# TPDH-Walrus.net
KiCad netlist of a schematic drawn in EAGLE
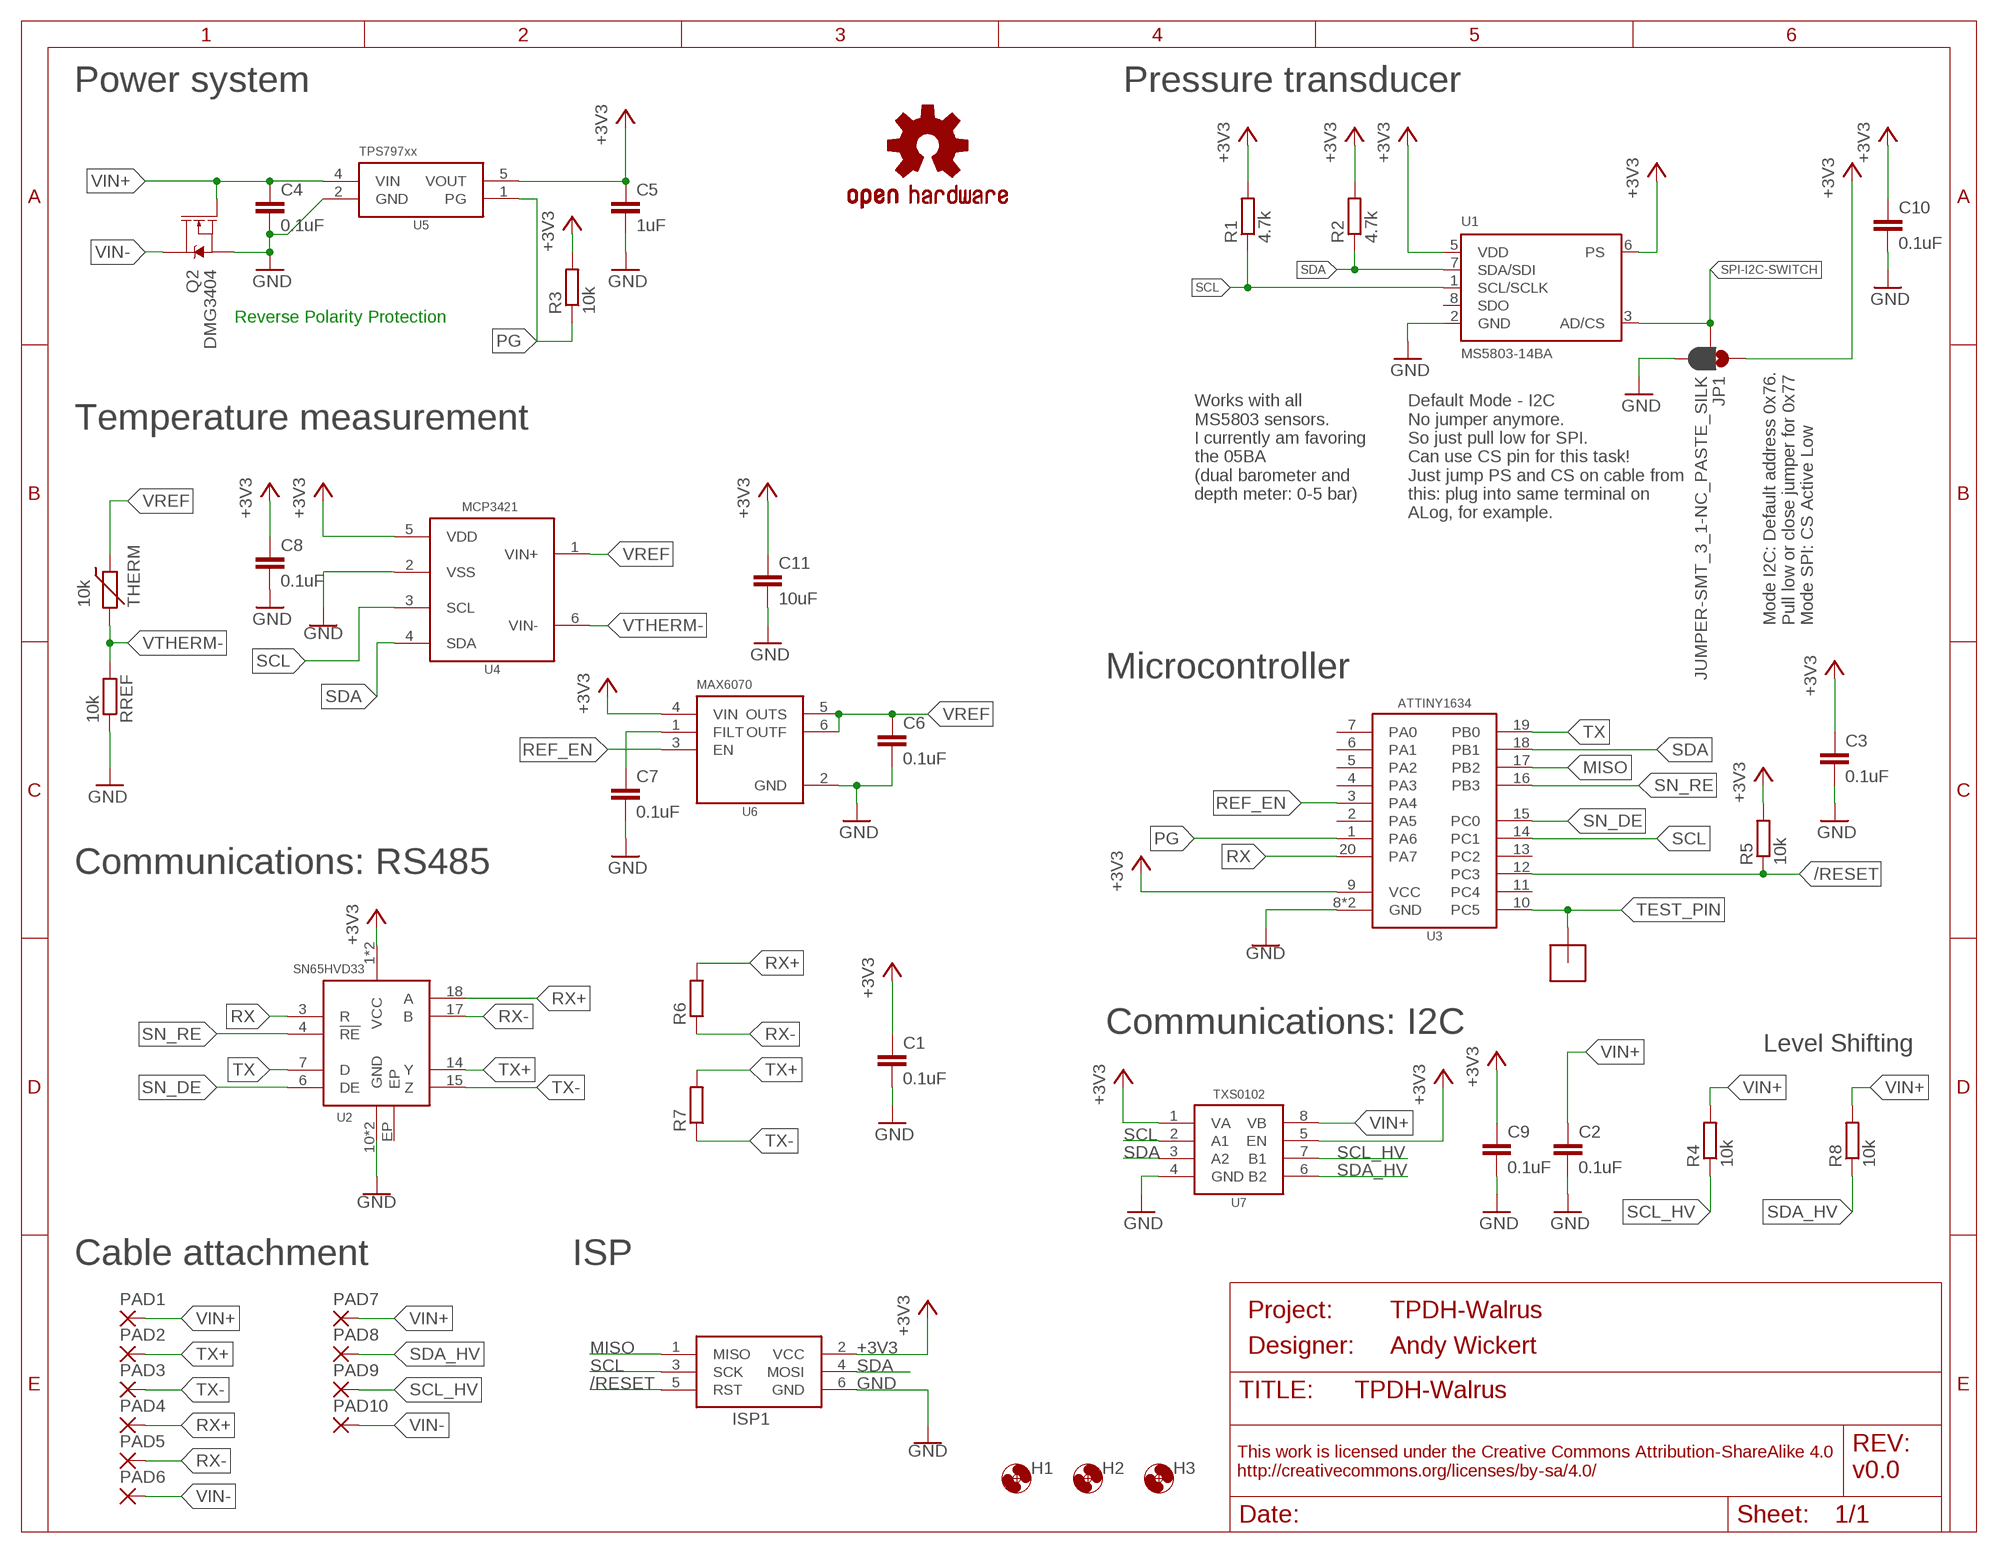
[diagram p0: schematic, sheet 1]

(export (version "E")
  (design (tool "Eeschema 10.0.6"))
  (components
    (comp (ref "C1")
      (value "0.1uF")
      (footprint "eagle-import:C0402")
      (fields (field (name "MF") "Murata") (field (name "MPN") "GCM155R71C104KA55D"))
      (libsource (lib "eagle-import") (part "C-EUC04020.1UF"))
    )
    (comp (ref "C2")
      (value "0.1uF")
      (footprint "eagle-import:C0402")
      (fields (field (name "MF") "Murata") (field (name "MPN") "GCM155R71C104KA55D"))
      (libsource (lib "eagle-import") (part "C-EUC04020.1UF"))
    )
    (comp (ref "C3")
      (value "0.1uF")
      (footprint "eagle-import:C0402")
      (fields (field (name "MF") "Murata") (field (name "MPN") "GCM155R71C104KA55D"))
      (libsource (lib "eagle-import") (part "C-EUC04020.1UF"))
    )
    (comp (ref "C4")
      (value "0.1uF")
      (footprint "eagle-import:C0402")
      (fields (field (name "MF") "Murata") (field (name "MPN") "GCM155R71C104KA55D"))
      (libsource (lib "eagle-import") (part "C-EUC04020.1UF"))
    )
    (comp (ref "C5")
      (value "1uF")
      (footprint "eagle-import:C0603")
      (fields (field (name "MF") "Murata") (field (name "MPN") "GRM188R61C105KA12D"))
      (libsource (lib "eagle-import") (part "bschulz_passives_C-EUC06031UF"))
    )
    (comp (ref "C6")
      (value "0.1uF")
      (footprint "eagle-import:C0402")
      (fields (field (name "MF") "Murata") (field (name "MPN") "GCM155R71C104KA55D"))
      (libsource (lib "eagle-import") (part "C-EUC04020.1UF"))
    )
    (comp (ref "C7")
      (value "0.1uF")
      (footprint "eagle-import:C0402")
      (fields (field (name "MF") "Murata") (field (name "MPN") "GCM155R71C104KA55D"))
      (libsource (lib "eagle-import") (part "C-EUC04020.1UF"))
    )
    (comp (ref "C8")
      (value "0.1uF")
      (footprint "eagle-import:C0402")
      (fields (field (name "MF") "Murata") (field (name "MPN") "GCM155R71C104KA55D"))
      (libsource (lib "eagle-import") (part "C-EUC04020.1UF"))
    )
    (comp (ref "C9")
      (value "0.1uF")
      (footprint "eagle-import:C0402")
      (fields (field (name "MF") "Murata") (field (name "MPN") "GCM155R71C104KA55D"))
      (libsource (lib "eagle-import") (part "C-EUC04020.1UF"))
    )
    (comp (ref "C10")
      (value "0.1uF")
      (footprint "eagle-import:C0402")
      (fields (field (name "MF") "Murata") (field (name "MPN") "GCM155R71C104KA55D"))
      (libsource (lib "eagle-import") (part "C-EUC04020.1UF"))
    )
    (comp (ref "C11")
      (value "10uF")
      (footprint "eagle-import:C0805")
      (fields (field (name "MF") "Samsung") (field (name "MPN") "CL21A106KQCLRNC"))
      (libsource (lib "eagle-import") (part "C-EUC080510UF"))
    )
    (comp (ref "H1")
      (value "MOUNTING_HOLE2_NP")
      (footprint "eagle-import:2_56")
      (libsource (lib "eagle-import") (part "MOUNTING_HOLE2_NP"))
    )
    (comp (ref "H2")
      (value "MOUNTING_HOLE2_NP")
      (footprint "eagle-import:2_56")
      (libsource (lib "eagle-import") (part "MOUNTING_HOLE2_NP"))
    )
    (comp (ref "H3")
      (value "MOUNTING_HOLE2_NP")
      (footprint "eagle-import:2_56")
      (libsource (lib "eagle-import") (part "MOUNTING_HOLE2_NP"))
    )
    (comp (ref "ISP1")
      (value "AVRISP-6")
      (footprint "eagle-import:AVRISP")
      (libsource (lib "eagle-import") (part "AVRISP-6"))
    )
    (comp (ref "JP1")
      (value "JUMPER-SMT_3_1-NC_PASTE_SILK")
      (footprint "eagle-import:SMT-JUMPER_3_1-NC_PASTE_SILK")
      (libsource (lib "eagle-import") (part "JUMPER-SMT_3_1-NC_PASTE_SILK"))
    )
    (comp (ref "LOGO1")
      (value "OSHW-LOGOM")
      (footprint "eagle-import:OSHW-LOGO-M")
      (libsource (lib "eagle-import") (part "OSHW-LOGOM"))
    )
    (comp (ref "PAD1")
      (value "2,15/1,0")
      (footprint "eagle-import:2,15_1,0")
      (libsource (lib "eagle-import") (part "2,15/1,0"))
    )
    (comp (ref "PAD2")
      (value "2,15/1,0")
      (footprint "eagle-import:2,15_1,0")
      (libsource (lib "eagle-import") (part "2,15/1,0"))
    )
    (comp (ref "PAD3")
      (value "2,15/1,0")
      (footprint "eagle-import:2,15_1,0")
      (libsource (lib "eagle-import") (part "2,15/1,0"))
    )
    (comp (ref "PAD4")
      (value "2,15/1,0")
      (footprint "eagle-import:2,15_1,0")
      (libsource (lib "eagle-import") (part "2,15/1,0"))
    )
    (comp (ref "PAD5")
      (value "2,15/1,0")
      (footprint "eagle-import:2,15_1,0")
      (libsource (lib "eagle-import") (part "2,15/1,0"))
    )
    (comp (ref "PAD6")
      (value "2,15/1,0")
      (footprint "eagle-import:2,15_1,0")
      (libsource (lib "eagle-import") (part "2,15/1,0"))
    )
    (comp (ref "PAD7")
      (value "2,15/1,0")
      (footprint "eagle-import:2,15_1,0")
      (libsource (lib "eagle-import") (part "2,15/1,0"))
    )
    (comp (ref "PAD8")
      (value "2,15/1,0")
      (footprint "eagle-import:2,15_1,0")
      (libsource (lib "eagle-import") (part "2,15/1,0"))
    )
    (comp (ref "PAD9")
      (value "2,15/1,0")
      (footprint "eagle-import:2,15_1,0")
      (libsource (lib "eagle-import") (part "2,15/1,0"))
    )
    (comp (ref "PAD10")
      (value "2,15/1,0")
      (footprint "eagle-import:2,15_1,0")
      (libsource (lib "eagle-import") (part "2,15/1,0"))
    )
    (comp (ref "Q2")
      (value "DMG3404")
      (footprint "eagle-import:SOT23-3")
      (fields (field (name "MF") "Diodes Incorporated") (field (name "MPN") "DMG3404L-7"))
      (libsource (lib "eagle-import") (part "MOSFET-NCH-DMG3404L"))
    )
    (comp (ref "R1")
      (value "4.7k")
      (footprint "eagle-import:R0402")
      (fields (field (name "MF") "Yageo") (field (name "MPN") "RC0402JR-074K7L"))
      (libsource (lib "eagle-import") (part "R-EU_R04024.7K"))
    )
    (comp (ref "R2")
      (value "4.7k")
      (footprint "eagle-import:R0402")
      (fields (field (name "MF") "Yageo") (field (name "MPN") "RC0402JR-074K7L"))
      (libsource (lib "eagle-import") (part "R-EU_R04024.7K"))
    )
    (comp (ref "R3")
      (value "10k")
      (footprint "eagle-import:R0402")
      (fields (field (name "MF") "Yageo") (field (name "MPN") "RC0402JR-0710KL"))
      (libsource (lib "eagle-import") (part "R-EU_R040210K"))
    )
    (comp (ref "R4")
      (value "10k")
      (footprint "eagle-import:R0402")
      (fields (field (name "MF") "Yageo") (field (name "MPN") "RC0402JR-0710KL"))
      (libsource (lib "eagle-import") (part "R-EU_R040210K"))
    )
    (comp (ref "R5")
      (value "10k")
      (footprint "eagle-import:R0402")
      (fields (field (name "MF") "Yageo") (field (name "MPN") "RC0402JR-0710KL"))
      (libsource (lib "eagle-import") (part "R-EU_R040210K"))
    )
    (comp (ref "R6")
      (value "R-EU_100R0402")
      (footprint "eagle-import:R0402")
      (fields
        (field (name "MF") "Yageo")
        (field (name "MPN") "RC0402FR-07100RL")
        (field (name "VALUE_PART") "100")
      )
      (libsource (lib "eagle-import") (part "R-EU_R0402100"))
    )
    (comp (ref "R7")
      (value "R-EU_100R0402")
      (footprint "eagle-import:R0402")
      (fields
        (field (name "MF") "Yageo")
        (field (name "MPN") "RC0402FR-07100RL")
        (field (name "VALUE_PART") "100")
      )
      (libsource (lib "eagle-import") (part "R-EU_R0402100"))
    )
    (comp (ref "R8")
      (value "10k")
      (footprint "eagle-import:R0402")
      (fields (field (name "MF") "Yageo") (field (name "MPN") "RC0402JR-0710KL"))
      (libsource (lib "eagle-import") (part "R-EU_R040210K"))
    )
    (comp (ref "RREF")
      (value "10k")
      (footprint "eagle-import:R0603")
      (fields
        (field (name "MF") "Panasonic")
        (field (name "MPN") "ERA-3AEB103V")
        (field (name "DIGIKEY") "P10KDBCT-ND")
        (field (name "MF_1") "Panasonic")
        (field (name "MPN_1") "ERA-3AEB103V")
      )
      (libsource (lib "eagle-import") (part "R-EU_R0603P10K"))
    )
    (comp (ref "THERM")
      (value "10k")
      (footprint "eagle-import:R0603")
      (fields
        (field (name "MF") "Murata")
        (field (name "MPN") "NCU18XH103F60RB")
        (field (name "MF_1") "Murata")
      )
      (libsource (lib "eagle-import") (part "THERMISTOR10K"))
    )
    (comp (ref "U$12")
      (value "POGO_PAD")
      (footprint "eagle-import:POGO_PAD")
      (libsource (lib "eagle-import") (part "POGO_PAD"))
    )
    (comp (ref "U1")
      (value "MS5803-14BA")
      (footprint "eagle-import:MS5803")
      (fields (field (name "MF") "TE") (field (name "MPN") "MS580305BA01-00"))
      (libsource (lib "eagle-import") (part "MS5803-14BA"))
    )
    (comp (ref "U2")
      (value "SN65HVD33RHL")
      (footprint "eagle-import:VQFN-20_POWER")
      (fields (field (name "MF") "TI") (field (name "MPN") "SN65HVD33RHLR"))
      (libsource (lib "eagle-import") (part "SN65HVD33RHL"))
    )
    (comp (ref "U3")
      (value "ATTINY1634QFN")
      (footprint "eagle-import:QFN20")
      (fields (field (name "MF") "Atmel") (field (name "MPN") "ATTINY1634-MUR"))
      (libsource (lib "eagle-import") (part "ATTINY1634QFN"))
    )
    (comp (ref "U4")
      (value "MCP3421A3")
      (footprint "eagle-import:SOT23-6L")
      (fields
        (field (name "DISP") "MCP3421")
        (field (name "MF") "Microchip")
        (field (name "MPN") "MCP3421A3T-E/CH")
      )
      (libsource (lib "eagle-import") (part "MCP3421A3"))
    )
    (comp (ref "U5")
      (value "TPS79733")
      (footprint "eagle-import:DCK_R-PDSO-G5")
      (fields (field (name "MF") "TI") (field (name "MPN") "TPS79733DCKR"))
      (libsource (lib "eagle-import") (part "TPS79733"))
    )
    (comp (ref "U6")
      (value "MAX6070AAUT18")
      (footprint "eagle-import:SOT23-6L")
      (fields (field (name "MF") "Maxim") (field (name "MPN") "MAX6070BAUT18+T"))
      (libsource (lib "eagle-import") (part "MAX6070AAUT18"))
    )
    (comp (ref "U7")
      (value "TXS0102DQM")
      (footprint "eagle-import:DQM_R-PX2SON-N8")
      (fields (field (name "MF") "TI") (field (name "MPN") "TXS0102DQMR"))
      (libsource (lib "eagle-import") (part "TXS0102DQM"))
    )
  )
  (nets
    (net (code "1") (name "+3V3") (class "Default")
      (node (ref "C1") (pin "1") (pinfunction "1_1") (pintype "passive"))
      (node (ref "C10") (pin "1") (pinfunction "1_1") (pintype "passive"))
      (node (ref "C11") (pin "1") (pinfunction "1_1") (pintype "passive"))
      (node (ref "C3") (pin "1") (pinfunction "1_1") (pintype "passive"))
      (node (ref "C5") (pin "1") (pinfunction "1_1") (pintype "passive"))
      (node (ref "C8") (pin "1") (pinfunction "1_1") (pintype "passive"))
      (node (ref "C9") (pin "1") (pinfunction "1_1") (pintype "passive"))
      (node (ref "ISP1") (pin "2") (pinfunction "VCC_2") (pintype "power_in"))
      (node (ref "JP1") (pin "1") (pinfunction "1_1") (pintype "passive"))
      (node (ref "R1") (pin "2") (pinfunction "2_2") (pintype "passive"))
      (node (ref "R2") (pin "2") (pinfunction "2_2") (pintype "passive"))
      (node (ref "R3") (pin "2") (pinfunction "2_2") (pintype "passive"))
      (node (ref "R5") (pin "2") (pinfunction "2_2") (pintype "passive"))
      (node (ref "U1") (pin "5") (pinfunction "VDD_5") (pintype "bidirectional"))
      (node (ref "U1") (pin "6") (pinfunction "PS_6") (pintype "bidirectional"))
      (node (ref "U2") (pin "1") (pinfunction "VCC_1") (pintype "power_in"))
      (node (ref "U2") (pin "20") (pinfunction "VCC_20") (pintype "power_in"))
      (node (ref "U3") (pin "9") (pinfunction "VCC_9") (pintype "power_in"))
      (node (ref "U4") (pin "5") (pinfunction "VDD_5") (pintype "passive"))
      (node (ref "U5") (pin "5") (pinfunction "VOUT_5") (pintype "bidirectional"))
      (node (ref "U6") (pin "4") (pinfunction "VIN_4") (pintype "bidirectional"))
      (node (ref "U7") (pin "1") (pinfunction "VA_1") (pintype "power_in"))
      (node (ref "U7") (pin "5") (pinfunction "EN_5") (pintype "input"))
    )
    (net (code "2") (name "GND") (class "Default")
      (node (ref "C1") (pin "2") (pinfunction "2_2") (pintype "passive"))
      (node (ref "C10") (pin "2") (pinfunction "2_2") (pintype "passive"))
      (node (ref "C11") (pin "2") (pinfunction "2_2") (pintype "passive"))
      (node (ref "C2") (pin "2") (pinfunction "2_2") (pintype "passive"))
      (node (ref "C3") (pin "2") (pinfunction "2_2") (pintype "passive"))
      (node (ref "C4") (pin "2") (pinfunction "2_2") (pintype "passive"))
      (node (ref "C5") (pin "2") (pinfunction "2_2") (pintype "passive"))
      (node (ref "C6") (pin "2") (pinfunction "2_2") (pintype "passive"))
      (node (ref "C7") (pin "2") (pinfunction "2_2") (pintype "passive"))
      (node (ref "C8") (pin "2") (pinfunction "2_2") (pintype "passive"))
      (node (ref "C9") (pin "2") (pinfunction "2_2") (pintype "passive"))
      (node (ref "ISP1") (pin "6") (pinfunction "GND_6") (pintype "power_in"))
      (node (ref "JP1") (pin "3") (pinfunction "3_3") (pintype "passive"))
      (node (ref "Q2") (pin "2") (pinfunction "S_2") (pintype "bidirectional"))
      (node (ref "RREF") (pin "1") (pinfunction "1_1") (pintype "passive"))
      (node (ref "U1") (pin "2") (pinfunction "GND_2") (pintype "bidirectional"))
      (node (ref "U2") (pin "10") (pinfunction "GND_10") (pintype "power_in"))
      (node (ref "U2") (pin "11") (pinfunction "GND_11") (pintype "power_in"))
      (node (ref "U3") (pin "8") (pinfunction "GND_8") (pintype "power_in"))
      (node (ref "U3") (pin "EP") (pinfunction "GND_EP") (pintype "power_in"))
      (node (ref "U4") (pin "2") (pinfunction "VSS_2") (pintype "passive"))
      (node (ref "U5") (pin "2") (pinfunction "GND_2") (pintype "bidirectional"))
      (node (ref "U6") (pin "2") (pinfunction "GND_2") (pintype "bidirectional"))
      (node (ref "U7") (pin "4") (pinfunction "GND_4") (pintype "power_in"))
    )
    (net (code "3") (name "MISO") (class "Default")
      (node (ref "ISP1") (pin "1") (pinfunction "MISO_1") (pintype "input"))
      (node (ref "U3") (pin "17") (pinfunction "PB2_17") (pintype "bidirectional"))
    )
    (net (code "4") (name "Net-(U6-FILT)") (class "Default")
      (node (ref "C7") (pin "1") (pinfunction "1_1") (pintype "passive"))
      (node (ref "U6") (pin "1") (pinfunction "FILT_1") (pintype "bidirectional"))
    )
    (net (code "5") (name "PG") (class "Default")
      (node (ref "R3") (pin "1") (pinfunction "1_1") (pintype "passive"))
      (node (ref "U3") (pin "1") (pinfunction "PA6_1") (pintype "bidirectional"))
      (node (ref "U5") (pin "1") (pinfunction "PG_1") (pintype "bidirectional"))
    )
    (net (code "6") (name "REF_EN") (class "Default")
      (node (ref "U3") (pin "3") (pinfunction "PA4_3") (pintype "bidirectional"))
      (node (ref "U6") (pin "3") (pinfunction "EN_3") (pintype "bidirectional"))
    )
    (net (code "7") (name "RX") (class "Default")
      (node (ref "U2") (pin "3") (pinfunction "R_3") (pintype "output"))
      (node (ref "U3") (pin "20") (pinfunction "PA7_20") (pintype "bidirectional"))
    )
    (net (code "8") (name "RX+") (class "Default")
      (node (ref "PAD4") (pin "1") (pinfunction "P_1") (pintype "passive"))
      (node (ref "R6") (pin "2") (pinfunction "2_2") (pintype "passive"))
      (node (ref "U2") (pin "18") (pinfunction "A_18") (pintype "bidirectional"))
    )
    (net (code "9") (name "RX-") (class "Default")
      (node (ref "PAD5") (pin "1") (pinfunction "P_1") (pintype "passive"))
      (node (ref "R6") (pin "1") (pinfunction "1_1") (pintype "passive"))
      (node (ref "U2") (pin "17") (pinfunction "B_17") (pintype "bidirectional"))
    )
    (net (code "10") (name "SCL") (class "Default")
      (node (ref "ISP1") (pin "3") (pinfunction "SCK_3") (pintype "output"))
      (node (ref "R1") (pin "1") (pinfunction "1_1") (pintype "passive"))
      (node (ref "U1") (pin "1") (pinfunction "SCL/SCLK_1") (pintype "bidirectional"))
      (node (ref "U3") (pin "14") (pinfunction "PC1_14") (pintype "bidirectional"))
      (node (ref "U4") (pin "3") (pinfunction "SCL_3") (pintype "bidirectional"))
      (node (ref "U7") (pin "2") (pinfunction "A1_2") (pintype "bidirectional"))
    )
    (net (code "11") (name "SCL_HV") (class "Default")
      (node (ref "PAD9") (pin "1") (pinfunction "P_1") (pintype "passive"))
      (node (ref "R4") (pin "1") (pinfunction "1_1") (pintype "passive"))
      (node (ref "U7") (pin "7") (pinfunction "B1_7") (pintype "bidirectional"))
    )
    (net (code "12") (name "SDA") (class "Default")
      (node (ref "ISP1") (pin "4") (pinfunction "MOSI_4") (pintype "output"))
      (node (ref "R2") (pin "1") (pinfunction "1_1") (pintype "passive"))
      (node (ref "U1") (pin "7") (pinfunction "SDA/SDI_7") (pintype "bidirectional"))
      (node (ref "U3") (pin "18") (pinfunction "PB1_18") (pintype "bidirectional"))
      (node (ref "U4") (pin "4") (pinfunction "SDA_4") (pintype "bidirectional"))
      (node (ref "U7") (pin "3") (pinfunction "A2_3") (pintype "bidirectional"))
    )
    (net (code "13") (name "SDA_HV") (class "Default")
      (node (ref "PAD8") (pin "1") (pinfunction "P_1") (pintype "passive"))
      (node (ref "R8") (pin "1") (pinfunction "1_1") (pintype "passive"))
      (node (ref "U7") (pin "6") (pinfunction "B2_6") (pintype "bidirectional"))
    )
    (net (code "14") (name "SN_DE") (class "Default")
      (node (ref "U2") (pin "6") (pinfunction "DE_6") (pintype "input"))
      (node (ref "U3") (pin "15") (pinfunction "PC0_15") (pintype "bidirectional"))
    )
    (net (code "15") (name "SN_RE") (class "Default")
      (node (ref "U2") (pin "4") (pinfunction "~{RE}_4") (pintype "input"))
      (node (ref "U3") (pin "16") (pinfunction "PB3_16") (pintype "bidirectional"))
    )
    (net (code "16") (name "SPI-I2C-SWITCH") (class "Default")
      (node (ref "JP1") (pin "2") (pinfunction "2_2") (pintype "passive"))
      (node (ref "U1") (pin "3") (pinfunction "AD/CS_3") (pintype "bidirectional"))
    )
    (net (code "17") (name "TEST_PIN") (class "Default")
      (node (ref "U$12") (pin "P$1") (pinfunction "P$1_P$1") (pintype "bidirectional"))
      (node (ref "U3") (pin "10") (pinfunction "PC5_10") (pintype "bidirectional"))
    )
    (net (code "18") (name "TX") (class "Default")
      (node (ref "U2") (pin "7") (pinfunction "D_7") (pintype "input"))
      (node (ref "U3") (pin "19") (pinfunction "PB0_19") (pintype "bidirectional"))
    )
    (net (code "19") (name "TX+") (class "Default")
      (node (ref "PAD2") (pin "1") (pinfunction "P_1") (pintype "passive"))
      (node (ref "R7") (pin "2") (pinfunction "2_2") (pintype "passive"))
      (node (ref "U2") (pin "14") (pinfunction "Y_14") (pintype "bidirectional"))
    )
    (net (code "20") (name "TX-") (class "Default")
      (node (ref "PAD3") (pin "1") (pinfunction "P_1") (pintype "passive"))
      (node (ref "R7") (pin "1") (pinfunction "1_1") (pintype "passive"))
      (node (ref "U2") (pin "15") (pinfunction "Z_15") (pintype "bidirectional"))
    )
    (net (code "21") (name "VIN+") (class "Default")
      (node (ref "C2") (pin "1") (pinfunction "1_1") (pintype "passive"))
      (node (ref "C4") (pin "1") (pinfunction "1_1") (pintype "passive"))
      (node (ref "PAD1") (pin "1") (pinfunction "P_1") (pintype "passive"))
      (node (ref "PAD7") (pin "1") (pinfunction "P_1") (pintype "passive"))
      (node (ref "Q2") (pin "1") (pinfunction "G_1") (pintype "bidirectional"))
      (node (ref "R4") (pin "2") (pinfunction "2_2") (pintype "passive"))
      (node (ref "R8") (pin "2") (pinfunction "2_2") (pintype "passive"))
      (node (ref "U5") (pin "4") (pinfunction "VIN_4") (pintype "bidirectional"))
      (node (ref "U7") (pin "8") (pinfunction "VB_8") (pintype "power_in"))
    )
    (net (code "22") (name "VIN-") (class "Default")
      (node (ref "PAD10") (pin "1") (pinfunction "P_1") (pintype "passive"))
      (node (ref "PAD6") (pin "1") (pinfunction "P_1") (pintype "passive"))
      (node (ref "Q2") (pin "3") (pinfunction "D_3") (pintype "bidirectional"))
    )
    (net (code "23") (name "VREF") (class "Default")
      (node (ref "C6") (pin "1") (pinfunction "1_1") (pintype "passive"))
      (node (ref "THERM") (pin "1") (pinfunction "2_1") (pintype "passive"))
      (node (ref "U4") (pin "1") (pinfunction "VIN+_1") (pintype "input"))
      (node (ref "U6") (pin "5") (pinfunction "OUTS_5") (pintype "bidirectional"))
      (node (ref "U6") (pin "6") (pinfunction "OUTF_6") (pintype "bidirectional"))
    )
    (net (code "24") (name "VTHERM-") (class "Default")
      (node (ref "RREF") (pin "2") (pinfunction "2_2") (pintype "passive"))
      (node (ref "THERM") (pin "2") (pinfunction "1_2") (pintype "passive"))
      (node (ref "U4") (pin "6") (pinfunction "VIN-_6") (pintype "input"))
    )
    (net (code "25") (name "unconnected-(U1-SDO-Pad8)") (class "Default")
      (node (ref "U1") (pin "8") (pinfunction "SDO_8") (pintype "bidirectional"))
    )
    (net (code "26") (name "unconnected-(U2-PadEP)") (class "Default")
      (node (ref "U2") (pin "EP") (pinfunction "EP_EP") (pintype "no_connect"))
    )
    (net (code "27") (name "unconnected-(U3-PA0-Pad7)") (class "Default")
      (node (ref "U3") (pin "7") (pinfunction "PA0_7") (pintype "bidirectional"))
    )
    (net (code "28") (name "unconnected-(U3-PA1-Pad6)") (class "Default")
      (node (ref "U3") (pin "6") (pinfunction "PA1_6") (pintype "bidirectional"))
    )
    (net (code "29") (name "unconnected-(U3-PA2-Pad5)") (class "Default")
      (node (ref "U3") (pin "5") (pinfunction "PA2_5") (pintype "bidirectional"))
    )
    (net (code "30") (name "unconnected-(U3-PA3-Pad4)") (class "Default")
      (node (ref "U3") (pin "4") (pinfunction "PA3_4") (pintype "bidirectional"))
    )
    (net (code "31") (name "unconnected-(U3-PA5-Pad2)") (class "Default")
      (node (ref "U3") (pin "2") (pinfunction "PA5_2") (pintype "bidirectional"))
    )
    (net (code "32") (name "unconnected-(U3-PC2-Pad13)") (class "Default")
      (node (ref "U3") (pin "13") (pinfunction "PC2_13") (pintype "bidirectional"))
    )
    (net (code "33") (name "unconnected-(U3-PC4-Pad11)") (class "Default")
      (node (ref "U3") (pin "11") (pinfunction "PC4_11") (pintype "bidirectional"))
    )
    (net (code "34") (name "{slash}RESET") (class "Default")
      (node (ref "ISP1") (pin "5") (pinfunction "RST_5") (pintype "output"))
      (node (ref "R5") (pin "1") (pinfunction "1_1") (pintype "passive"))
      (node (ref "U3") (pin "12") (pinfunction "PC3_12") (pintype "bidirectional"))
    )
  )
)
